# pedometer.net
KiCad netlist of a schematic drawn in EAGLE
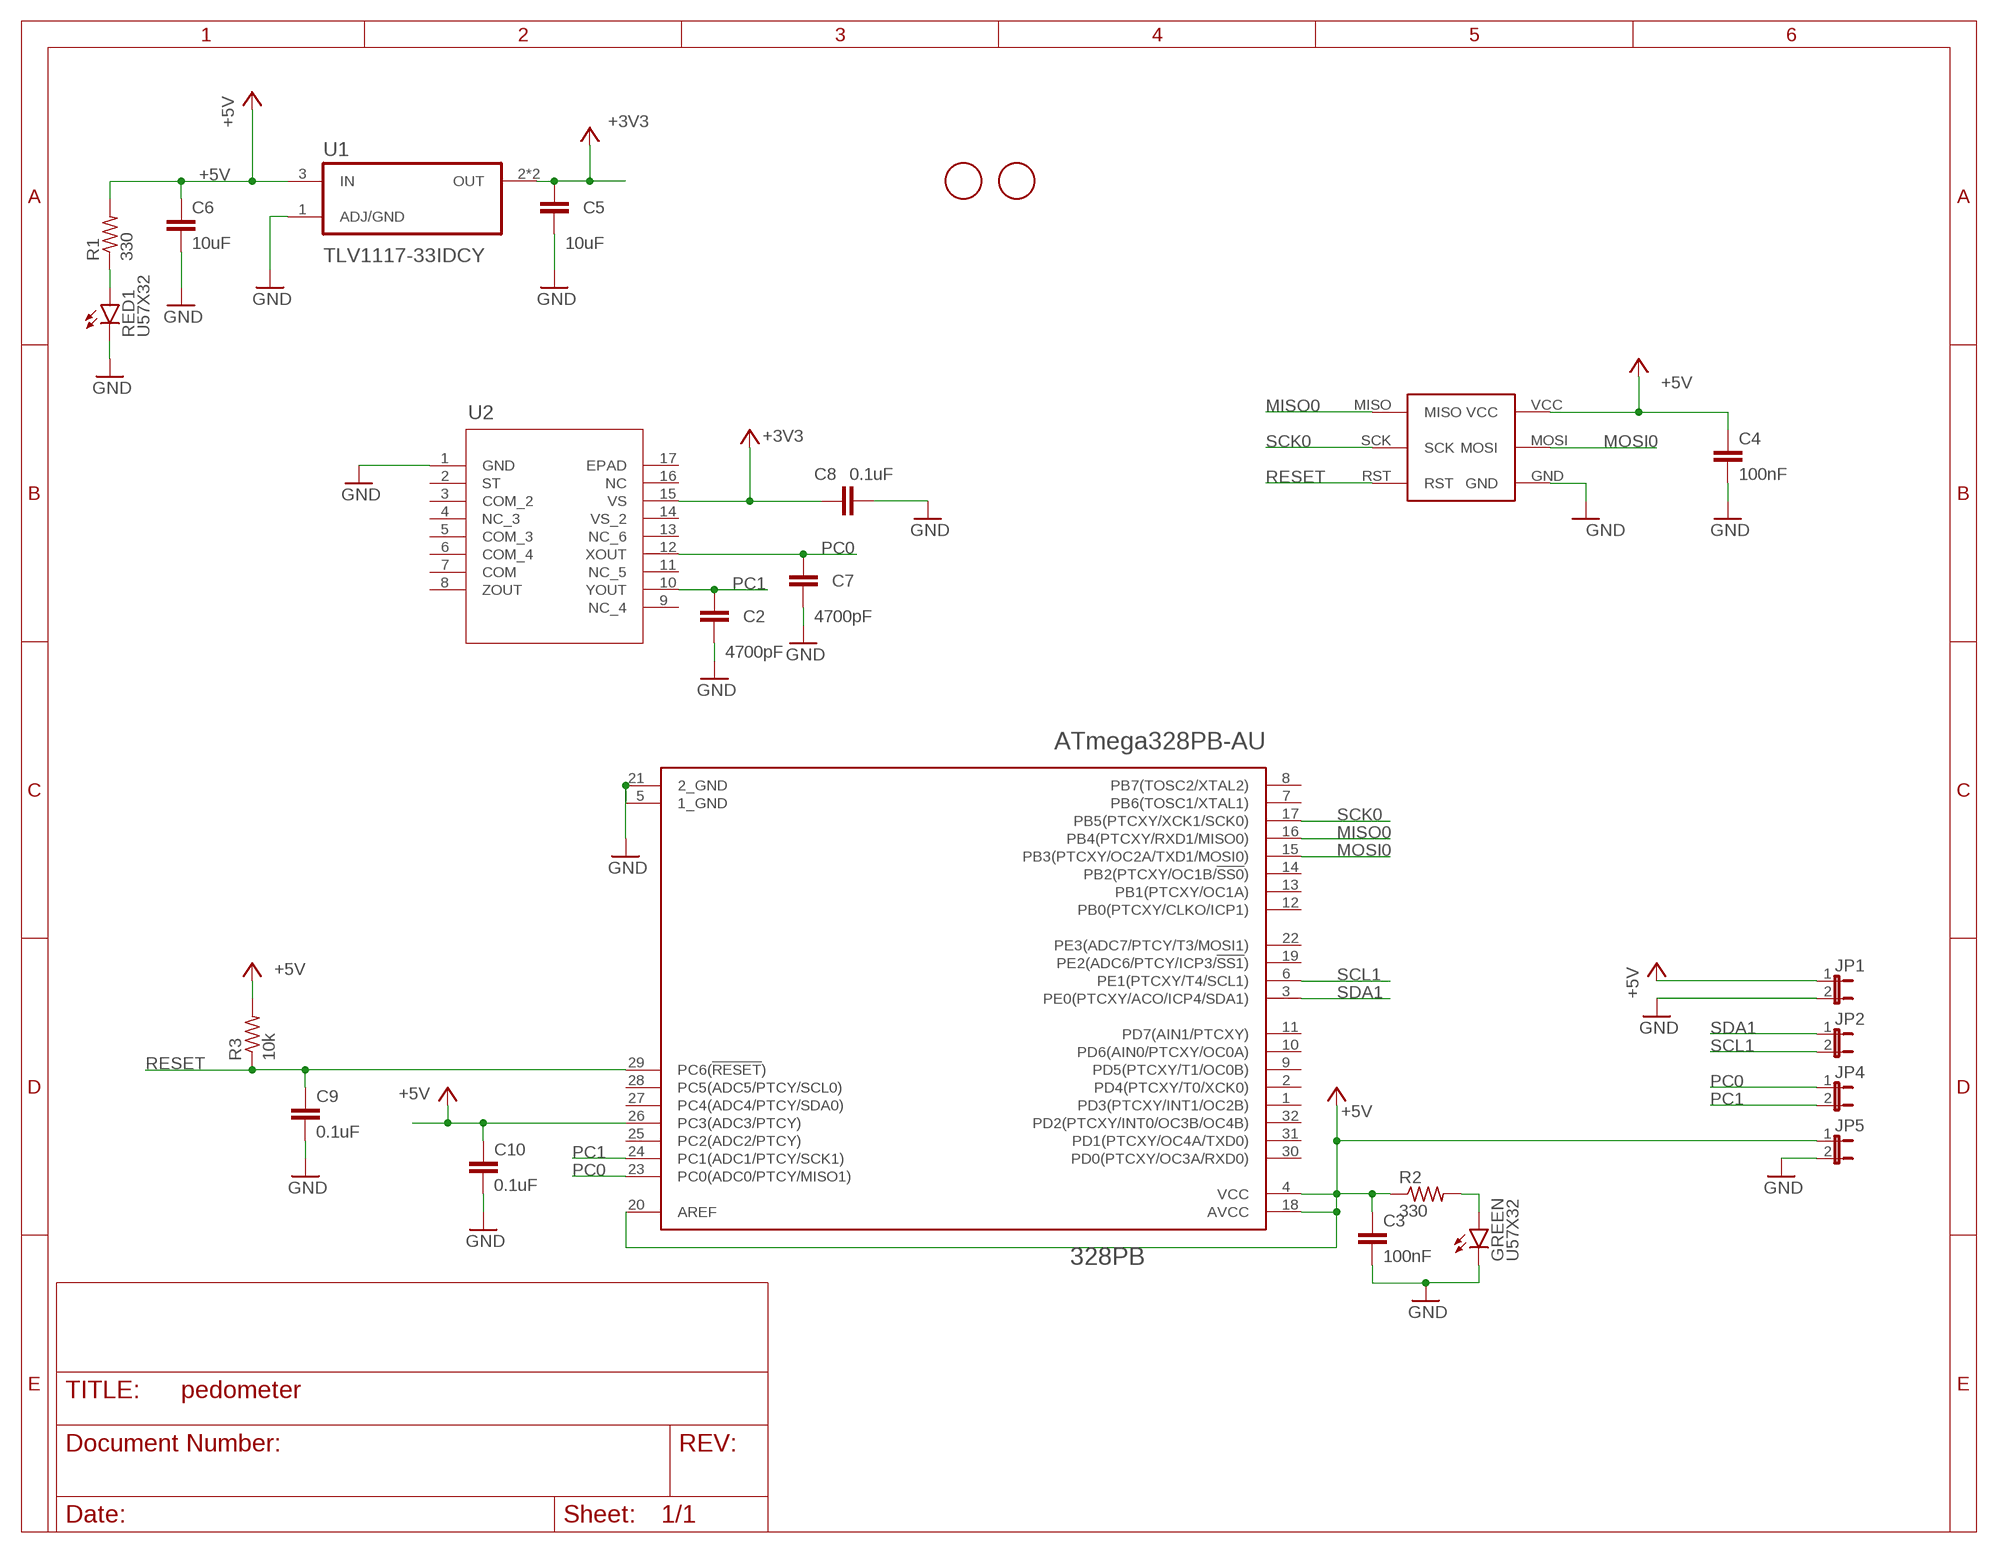
[diagram p0: schematic, sheet 1]

(export (version "E")
  (design (tool "Eeschema 10.0.6"))
  (components
    (comp (ref "328PB")
      (value "MICROCHIP_ATMEGA328PB-AUMICROCHIP_ATMEGA328PB-AU_0_0")
      (footprint "eagle-import:MICROCHIP_ATMEGA328PB-AU_0")
      (fields
        (field (name "DIGIKEY_PART_NUMBER") "ATMEGA328PB-AU-ND")
        (field (name "MF") "Microchip")
        (field (name "MOUSER_PART_NUMBER") "556-ATMEGA328PB-AU")
      )
      (libsource (lib "eagle-import") (part "MICROCHIP_ATMEGA328PB-AUMICROCHIP_ATMEGA328PB-AU_0_0"))
    )
    (comp (ref "C2")
      (value "4700pF")
      (footprint "eagle-import:C0805K")
      (libsource (lib "eagle-import") (part "C-EUC0805K"))
    )
    (comp (ref "C3")
      (value "100nF")
      (footprint "eagle-import:C0805K")
      (libsource (lib "eagle-import") (part "C-EUC0805K"))
    )
    (comp (ref "C4")
      (value "100nF")
      (footprint "eagle-import:C0805K")
      (libsource (lib "eagle-import") (part "C-EUC0805K"))
    )
    (comp (ref "C5")
      (value "10uF")
      (footprint "eagle-import:C0805K")
      (libsource (lib "eagle-import") (part "C-EUC0805K"))
    )
    (comp (ref "C6")
      (value "10uF")
      (footprint "eagle-import:C0805K")
      (libsource (lib "eagle-import") (part "C-EUC0805K"))
    )
    (comp (ref "C7")
      (value "4700pF")
      (footprint "eagle-import:C0805K")
      (libsource (lib "eagle-import") (part "C-EUC0805K"))
    )
    (comp (ref "C8")
      (value "0.1uF")
      (footprint "eagle-import:C0805K")
      (libsource (lib "eagle-import") (part "C-EUC0805K"))
    )
    (comp (ref "C9")
      (value "0.1uF")
      (footprint "eagle-import:C0805K")
      (libsource (lib "eagle-import") (part "C-EUC0805K"))
    )
    (comp (ref "C10")
      (value "0.1uF")
      (footprint "eagle-import:C0805K")
      (libsource (lib "eagle-import") (part "C-EUC0805K"))
    )
    (comp (ref "GREEN")
      (value "U57X32")
      (footprint "eagle-import:U57X32")
      (libsource (lib "eagle-import") (part "U57X32"))
    )
    (comp (ref "JP1")
      (value "JP1E")
      (footprint "eagle-import:JP1")
      (libsource (lib "eagle-import") (part "JP1E"))
    )
    (comp (ref "JP2")
      (value "JP1E")
      (footprint "eagle-import:JP1")
      (libsource (lib "eagle-import") (part "JP1E"))
    )
    (comp (ref "JP4")
      (value "JP1E")
      (footprint "eagle-import:JP1")
      (libsource (lib "eagle-import") (part "JP1E"))
    )
    (comp (ref "JP5")
      (value "JP1E")
      (footprint "eagle-import:JP1")
      (libsource (lib "eagle-import") (part "JP1E"))
    )
    (comp (ref "R1")
      (value "330")
      (footprint "eagle-import:R0805")
      (libsource (lib "eagle-import") (part "R-US_R0805"))
    )
    (comp (ref "R2")
      (value "330")
      (footprint "eagle-import:R0805")
      (libsource (lib "eagle-import") (part "R-US_R0805"))
    )
    (comp (ref "R3")
      (value "10k")
      (footprint "eagle-import:R0805")
      (libsource (lib "eagle-import") (part "R-US_R0805"))
    )
    (comp (ref "RED1")
      (value "U57X32")
      (footprint "eagle-import:U57X32")
      (libsource (lib "eagle-import") (part "U57X32"))
    )
    (comp (ref "U$1")
      (value "AVR-ISP")
      (footprint "eagle-import:AVR-ISP")
      (fields (field (name "MF") "Gravitech"))
      (libsource (lib "eagle-import") (part "AVR-ISP"))
    )
    (comp (ref "U$2")
      (value "FIDUCIAL")
      (footprint "eagle-import:FIDUCIAL_1MM")
      (libsource (lib "eagle-import") (part "FIDUCIAL"))
    )
    (comp (ref "U$3")
      (value "FIDUCIAL")
      (footprint "eagle-import:FIDUCIAL_1MM")
      (libsource (lib "eagle-import") (part "FIDUCIAL"))
    )
    (comp (ref "U1")
      (value "TLV1117-33IDCY")
      (footprint "eagle-import:SOT230P700X180-4N")
      (fields (field (name "MF") "Texas Instruments"))
      (libsource (lib "eagle-import") (part "TLV1117-33IDCY"))
    )
    (comp (ref "U2")
      (value "ADXL327BCPZ-RL7CP_16_5A_ADI-M")
      (footprint "eagle-import:CP_16_5A_ADI-M")
      (fields
        (field (name "MANUFACTURER_PART_NUMBER") "ADXL327BCPZ-RL7")
        (field (name "COPYRIGHT") "Copyright (C) 2018 Accelerated Designs. All rights reserved")
      )
      (libsource (lib "eagle-import") (part "ADXL327BCPZ-RL7CP_16_5A_ADI-M"))
    )
  )
  (nets
    (net (code "1") (name "+3V3") (class "Default")
      (node (ref "C5") (pin "2") (pinfunction "2_2") (pintype "passive"))
      (node (ref "C8") (pin "2") (pinfunction "2_2") (pintype "passive"))
      (node (ref "U1") (pin "2") (pinfunction "OUT_2") (pintype "output"))
      (node (ref "U1") (pin "4") (pinfunction "OUT_4") (pintype "output"))
      (node (ref "U2") (pin "15") (pinfunction "VS_15") (pintype "passive"))
    )
    (net (code "2") (name "+5V") (class "Default")
      (node (ref "328PB") (pin "18") (pinfunction "AVCC_18") (pintype "bidirectional"))
      (node (ref "328PB") (pin "20") (pinfunction "AREF_20") (pintype "bidirectional"))
      (node (ref "328PB") (pin "26") (pinfunction "PC3(ADC3/PTCY)_26") (pintype "bidirectional"))
      (node (ref "328PB") (pin "4") (pinfunction "VCC_4") (pintype "bidirectional"))
      (node (ref "C10") (pin "2") (pinfunction "2_2") (pintype "passive"))
      (node (ref "C3") (pin "2") (pinfunction "2_2") (pintype "passive"))
      (node (ref "C4") (pin "2") (pinfunction "2_2") (pintype "passive"))
      (node (ref "C6") (pin "2") (pinfunction "2_2") (pintype "passive"))
      (node (ref "JP1") (pin "1") (pinfunction "1_1") (pintype "passive"))
      (node (ref "JP5") (pin "1") (pinfunction "1_1") (pintype "passive"))
      (node (ref "R1") (pin "2") (pinfunction "2_2") (pintype "passive"))
      (node (ref "R2") (pin "1") (pinfunction "1_1") (pintype "passive"))
      (node (ref "R3") (pin "2") (pinfunction "2_2") (pintype "passive"))
      (node (ref "U$1") (pin "VCC") (pinfunction "VCC_VCC") (pintype "bidirectional"))
      (node (ref "U1") (pin "3") (pinfunction "IN_3") (pintype "input"))
    )
    (net (code "3") (name "/MISO0") (class "Default")
      (node (ref "328PB") (pin "16") (pinfunction "PB4(PTCXY/RXD1/MISO0)_16") (pintype "bidirectional"))
      (node (ref "U$1") (pin "MISO") (pinfunction "MISO_MISO") (pintype "bidirectional"))
    )
    (net (code "4") (name "/MOSI0") (class "Default")
      (node (ref "328PB") (pin "15") (pinfunction "PB3(PTCXY/OC2A/TXD1/MOSI0)_15") (pintype "bidirectional"))
      (node (ref "U$1") (pin "MOSI") (pinfunction "MOSI_MOSI") (pintype "bidirectional"))
    )
    (net (code "5") (name "/PC0") (class "Default")
      (node (ref "328PB") (pin "23") (pinfunction "PC0(ADC0/PTCY/MISO1)_23") (pintype "bidirectional"))
      (node (ref "C7") (pin "2") (pinfunction "2_2") (pintype "passive"))
      (node (ref "JP4") (pin "1") (pinfunction "1_1") (pintype "passive"))
      (node (ref "U2") (pin "12") (pinfunction "XOUT_12") (pintype "output"))
    )
    (net (code "6") (name "/PC1") (class "Default")
      (node (ref "328PB") (pin "24") (pinfunction "PC1(ADC1/PTCY/SCK1)_24") (pintype "bidirectional"))
      (node (ref "C2") (pin "2") (pinfunction "2_2") (pintype "passive"))
      (node (ref "JP4") (pin "2") (pinfunction "2_2") (pintype "passive"))
      (node (ref "U2") (pin "10") (pinfunction "YOUT_10") (pintype "output"))
    )
    (net (code "7") (name "/RESET") (class "Default")
      (node (ref "328PB") (pin "29") (pinfunction "PC6(~{RESET})_29") (pintype "bidirectional"))
      (node (ref "C9") (pin "2") (pinfunction "2_2") (pintype "passive"))
      (node (ref "R3") (pin "1") (pinfunction "1_1") (pintype "passive"))
      (node (ref "U$1") (pin "RST") (pinfunction "RST_RST") (pintype "bidirectional"))
    )
    (net (code "8") (name "/SCK0") (class "Default")
      (node (ref "328PB") (pin "17") (pinfunction "PB5(PTCXY/XCK1/SCK0)_17") (pintype "bidirectional"))
      (node (ref "U$1") (pin "SCK") (pinfunction "SCK_SCK") (pintype "bidirectional"))
    )
    (net (code "9") (name "/SCL1") (class "Default")
      (node (ref "328PB") (pin "6") (pinfunction "PE1(PTCXY/T4/SCL1)_6") (pintype "bidirectional"))
      (node (ref "JP2") (pin "2") (pinfunction "2_2") (pintype "passive"))
    )
    (net (code "10") (name "/SDA1") (class "Default")
      (node (ref "328PB") (pin "3") (pinfunction "PE0(PTCXY/ACO/ICP4/SDA1)_3") (pintype "bidirectional"))
      (node (ref "JP2") (pin "1") (pinfunction "1_1") (pintype "passive"))
    )
    (net (code "11") (name "GND") (class "Default")
      (node (ref "328PB") (pin "21") (pinfunction "2_GND_21") (pintype "bidirectional"))
      (node (ref "328PB") (pin "5") (pinfunction "1_GND_5") (pintype "bidirectional"))
      (node (ref "C10") (pin "1") (pinfunction "1_1") (pintype "passive"))
      (node (ref "C2") (pin "1") (pinfunction "1_1") (pintype "passive"))
      (node (ref "C3") (pin "1") (pinfunction "1_1") (pintype "passive"))
      (node (ref "C4") (pin "1") (pinfunction "1_1") (pintype "passive"))
      (node (ref "C5") (pin "1") (pinfunction "1_1") (pintype "passive"))
      (node (ref "C6") (pin "1") (pinfunction "1_1") (pintype "passive"))
      (node (ref "C7") (pin "1") (pinfunction "1_1") (pintype "passive"))
      (node (ref "C8") (pin "1") (pinfunction "1_1") (pintype "passive"))
      (node (ref "C9") (pin "1") (pinfunction "1_1") (pintype "passive"))
      (node (ref "GREEN") (pin "K") (pinfunction "C_K") (pintype "passive"))
      (node (ref "JP1") (pin "2") (pinfunction "2_2") (pintype "passive"))
      (node (ref "JP5") (pin "2") (pinfunction "2_2") (pintype "passive"))
      (node (ref "RED1") (pin "K") (pinfunction "C_K") (pintype "passive"))
      (node (ref "U$1") (pin "GND") (pinfunction "GND_GND") (pintype "bidirectional"))
      (node (ref "U1") (pin "1") (pinfunction "ADJ/GND_1") (pintype "bidirectional"))
      (node (ref "U2") (pin "1") (pinfunction "GND_1") (pintype "bidirectional"))
    )
    (net (code "12") (name "Net-(GREEN-PadA)") (class "Default")
      (node (ref "GREEN") (pin "A") (pinfunction "A_A") (pintype "passive"))
      (node (ref "R2") (pin "2") (pinfunction "2_2") (pintype "passive"))
    )
    (net (code "13") (name "Net-(R1-Pad1)") (class "Default")
      (node (ref "R1") (pin "1") (pinfunction "1_1") (pintype "passive"))
      (node (ref "RED1") (pin "A") (pinfunction "A_A") (pintype "passive"))
    )
    (net (code "14") (name "unconnected-(328PB-PB0(PTCXY{slash}CLKO{slash}ICP1)-Pad12)") (class "Default")
      (node (ref "328PB") (pin "12") (pinfunction "PB0(PTCXY/CLKO/ICP1)_12") (pintype "bidirectional"))
    )
    (net (code "15") (name "unconnected-(328PB-PB1(PTCXY{slash}OC1A)-Pad13)") (class "Default")
      (node (ref "328PB") (pin "13") (pinfunction "PB1(PTCXY/OC1A)_13") (pintype "bidirectional"))
    )
    (net (code "16") (name "unconnected-(328PB-PB2(PTCXY{slash}OC1B{slash}~{SS0})-Pad14)") (class "Default")
      (node (ref "328PB") (pin "14") (pinfunction "PB2(PTCXY/OC1B/~{SS0})_14") (pintype "bidirectional"))
    )
    (net (code "17") (name "unconnected-(328PB-PB6(TOSC1{slash}XTAL1)-Pad7)") (class "Default")
      (node (ref "328PB") (pin "7") (pinfunction "PB6(TOSC1/XTAL1)_7") (pintype "bidirectional"))
    )
    (net (code "18") (name "unconnected-(328PB-PB7(TOSC2{slash}XTAL2)-Pad8)") (class "Default")
      (node (ref "328PB") (pin "8") (pinfunction "PB7(TOSC2/XTAL2)_8") (pintype "bidirectional"))
    )
    (net (code "19") (name "unconnected-(328PB-PC2(ADC2{slash}PTCY)-Pad25)") (class "Default")
      (node (ref "328PB") (pin "25") (pinfunction "PC2(ADC2/PTCY)_25") (pintype "bidirectional"))
    )
    (net (code "20") (name "unconnected-(328PB-PC4(ADC4{slash}PTCY{slash}SDA0)-Pad27)") (class "Default")
      (node (ref "328PB") (pin "27") (pinfunction "PC4(ADC4/PTCY/SDA0)_27") (pintype "bidirectional"))
    )
    (net (code "21") (name "unconnected-(328PB-PC5(ADC5{slash}PTCY{slash}SCL0)-Pad28)") (class "Default")
      (node (ref "328PB") (pin "28") (pinfunction "PC5(ADC5/PTCY/SCL0)_28") (pintype "bidirectional"))
    )
    (net (code "22") (name "unconnected-(328PB-PD0(PTCXY{slash}OC3A{slash}RXD0)-Pad30)") (class "Default")
      (node (ref "328PB") (pin "30") (pinfunction "PD0(PTCXY/OC3A/RXD0)_30") (pintype "bidirectional"))
    )
    (net (code "23") (name "unconnected-(328PB-PD1(PTCXY{slash}OC4A{slash}TXD0)-Pad31)") (class "Default")
      (node (ref "328PB") (pin "31") (pinfunction "PD1(PTCXY/OC4A/TXD0)_31") (pintype "bidirectional"))
    )
    (net (code "24") (name "unconnected-(328PB-PD2(PTCXY{slash}INT0{slash}OC3B{slash}OC4B)-Pad32)") (class "Default")
      (node (ref "328PB") (pin "32") (pinfunction "PD2(PTCXY/INT0/OC3B/OC4B)_32") (pintype "bidirectional"))
    )
    (net (code "25") (name "unconnected-(328PB-PD3(PTCXY{slash}INT1{slash}OC2B)-Pad1)") (class "Default")
      (node (ref "328PB") (pin "1") (pinfunction "PD3(PTCXY/INT1/OC2B)_1") (pintype "bidirectional"))
    )
    (net (code "26") (name "unconnected-(328PB-PD4(PTCXY{slash}T0{slash}XCK0)-Pad2)") (class "Default")
      (node (ref "328PB") (pin "2") (pinfunction "PD4(PTCXY/T0/XCK0)_2") (pintype "bidirectional"))
    )
    (net (code "27") (name "unconnected-(328PB-PD5(PTCXY{slash}T1{slash}OC0B)-Pad9)") (class "Default")
      (node (ref "328PB") (pin "9") (pinfunction "PD5(PTCXY/T1/OC0B)_9") (pintype "bidirectional"))
    )
    (net (code "28") (name "unconnected-(328PB-PD6(AIN0{slash}PTCXY{slash}OC0A)-Pad10)") (class "Default")
      (node (ref "328PB") (pin "10") (pinfunction "PD6(AIN0/PTCXY/OC0A)_10") (pintype "bidirectional"))
    )
    (net (code "29") (name "unconnected-(328PB-PD7(AIN1{slash}PTCXY)-Pad11)") (class "Default")
      (node (ref "328PB") (pin "11") (pinfunction "PD7(AIN1/PTCXY)_11") (pintype "bidirectional"))
    )
    (net (code "30") (name "unconnected-(328PB-PE2(ADC6{slash}PTCY{slash}ICP3{slash}~{SS1})-Pad19)") (class "Default")
      (node (ref "328PB") (pin "19") (pinfunction "PE2(ADC6/PTCY/ICP3/~{SS1})_19") (pintype "bidirectional"))
    )
    (net (code "31") (name "unconnected-(328PB-PE3(ADC7{slash}PTCY{slash}T3{slash}MOSI1)-Pad22)") (class "Default")
      (node (ref "328PB") (pin "22") (pinfunction "PE3(ADC7/PTCY/T3/MOSI1)_22") (pintype "bidirectional"))
    )
    (net (code "32") (name "unconnected-(U2-COM-Pad7)") (class "Default")
      (node (ref "U2") (pin "7") (pinfunction "COM_7") (pintype "passive"))
    )
    (net (code "33") (name "unconnected-(U2-COM_2-Pad3)") (class "Default")
      (node (ref "U2") (pin "3") (pinfunction "COM_2_3") (pintype "passive"))
    )
    (net (code "34") (name "unconnected-(U2-COM_3-Pad5)") (class "Default")
      (node (ref "U2") (pin "5") (pinfunction "COM_3_5") (pintype "passive"))
    )
    (net (code "35") (name "unconnected-(U2-COM_4-Pad6)") (class "Default")
      (node (ref "U2") (pin "6") (pinfunction "COM_4_6") (pintype "passive"))
    )
    (net (code "36") (name "unconnected-(U2-EPAD-Pad17)") (class "Default")
      (node (ref "U2") (pin "17") (pinfunction "EPAD_17") (pintype "passive"))
    )
    (net (code "37") (name "unconnected-(U2-NC-Pad16)") (class "Default")
      (node (ref "U2") (pin "16") (pinfunction "NC_16") (pintype "no_connect"))
    )
    (net (code "38") (name "unconnected-(U2-NC_3-Pad4)") (class "Default")
      (node (ref "U2") (pin "4") (pinfunction "NC_3_4") (pintype "no_connect"))
    )
    (net (code "39") (name "unconnected-(U2-NC_4-Pad9)") (class "Default")
      (node (ref "U2") (pin "9") (pinfunction "NC_4_9") (pintype "no_connect"))
    )
    (net (code "40") (name "unconnected-(U2-NC_5-Pad11)") (class "Default")
      (node (ref "U2") (pin "11") (pinfunction "NC_5_11") (pintype "no_connect"))
    )
    (net (code "41") (name "unconnected-(U2-NC_6-Pad13)") (class "Default")
      (node (ref "U2") (pin "13") (pinfunction "NC_6_13") (pintype "no_connect"))
    )
    (net (code "42") (name "unconnected-(U2-ST-Pad2)") (class "Default")
      (node (ref "U2") (pin "2") (pinfunction "ST_2") (pintype "passive"))
    )
    (net (code "43") (name "unconnected-(U2-VS_2-Pad14)") (class "Default")
      (node (ref "U2") (pin "14") (pinfunction "VS_2_14") (pintype "passive"))
    )
    (net (code "44") (name "unconnected-(U2-ZOUT-Pad8)") (class "Default")
      (node (ref "U2") (pin "8") (pinfunction "ZOUT_8") (pintype "output"))
    )
  )
)
